# Bypass_FPGA_3V3.net
KiCad netlist of a schematic drawn in Altium Designer
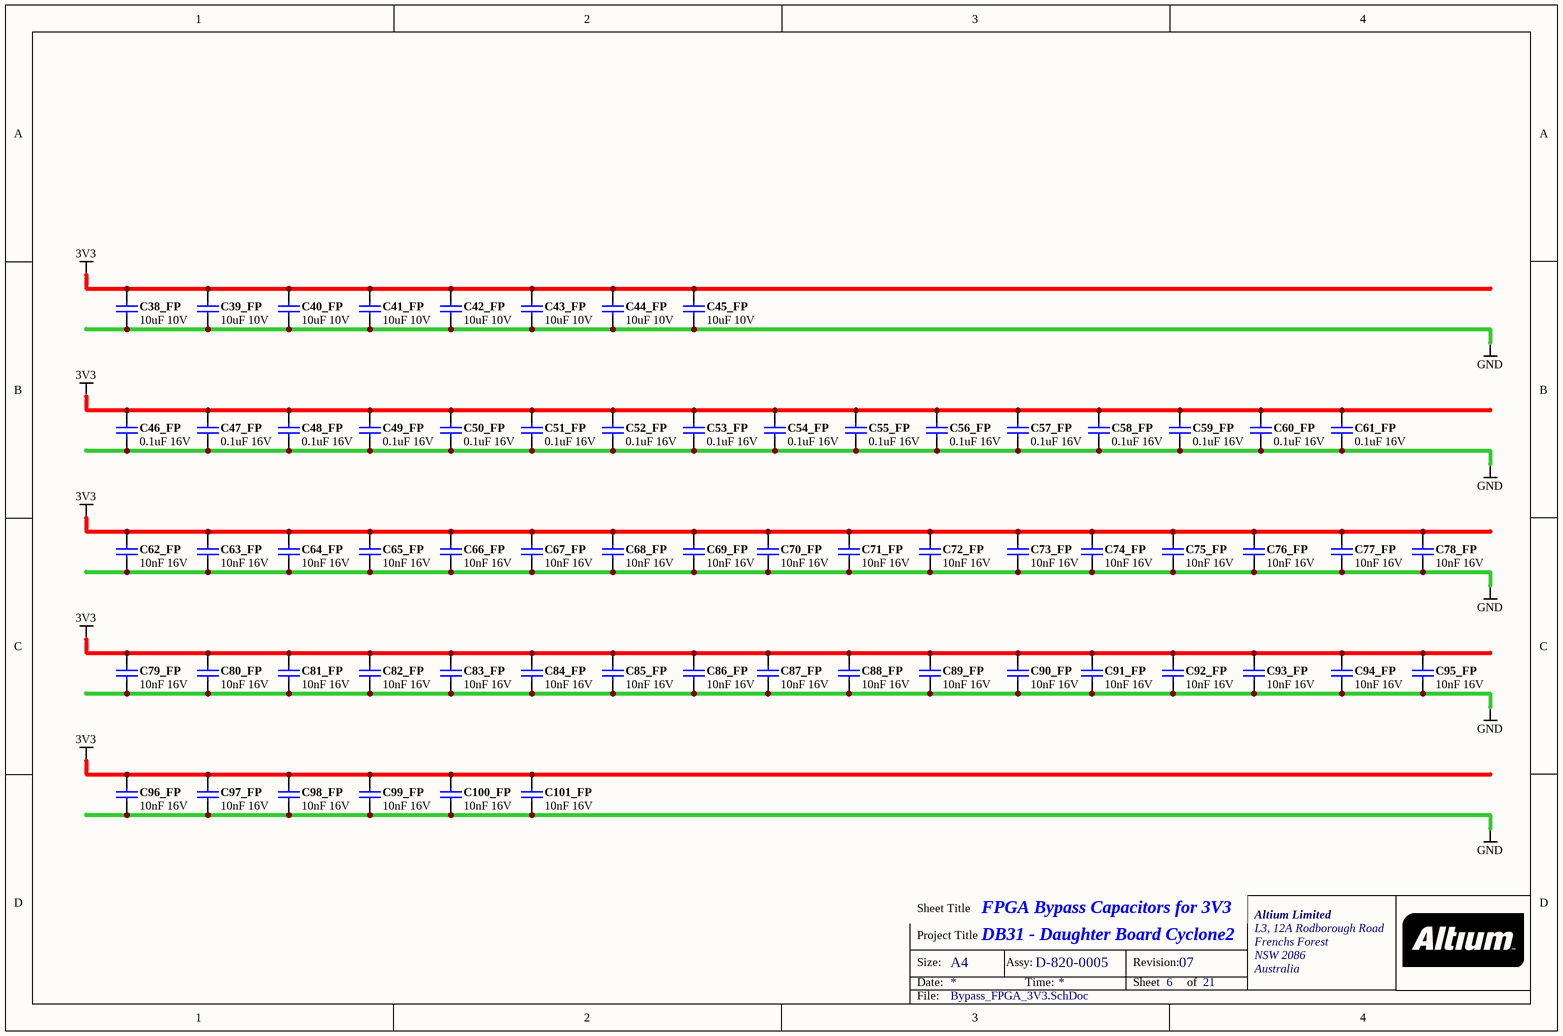
[diagram p0: Bypass_FPGA_3V3.SchDoc]

(export (version "E")
  (design (tool "Eeschema 10.0.6"))
  (components
    (comp (ref "C38_FP")
      (value "10uF 10V")
      (footprint "CAPC2012-STAR")
      (description "Capacitor, Ceramic, 10uF 10% 10V 0805 (2012) X5R")
      (fields (field (name "TOLERANCE") "10 %"))
      (libsource (lib "AltiumDesignLibrary") (part "CAP-NP"))
    )
    (comp (ref "C39_FP")
      (value "10uF 10V")
      (footprint "CAPC2012-STAR")
      (description "Capacitor, Ceramic, 10uF 10% 10V 0805 (2012) X5R")
      (fields (field (name "TOLERANCE") "10 %"))
      (libsource (lib "AltiumDesignLibrary") (part "CAP-NP"))
    )
    (comp (ref "C40_FP")
      (value "10uF 10V")
      (footprint "CAPC2012-STAR")
      (description "Capacitor, Ceramic, 10uF 10% 10V 0805 (2012) X5R")
      (fields (field (name "TOLERANCE") "10 %"))
      (libsource (lib "AltiumDesignLibrary") (part "CAP-NP"))
    )
    (comp (ref "C41_FP")
      (value "10uF 10V")
      (footprint "CAPC2012-STAR")
      (description "Capacitor, Ceramic, 10uF 10% 10V 0805 (2012) X5R")
      (fields (field (name "TOLERANCE") "10 %"))
      (libsource (lib "AltiumDesignLibrary") (part "CAP-NP"))
    )
    (comp (ref "C42_FP")
      (value "10uF 10V")
      (footprint "CAPC2012-STAR")
      (description "Capacitor, Ceramic, 10uF 10% 10V 0805 (2012) X5R")
      (fields (field (name "TOLERANCE") "10 %"))
      (libsource (lib "AltiumDesignLibrary") (part "CAP-NP"))
    )
    (comp (ref "C43_FP")
      (value "10uF 10V")
      (footprint "CAPC2012-STAR")
      (description "Capacitor, Ceramic, 10uF 10% 10V 0805 (2012) X5R")
      (fields (field (name "TOLERANCE") "10 %"))
      (libsource (lib "AltiumDesignLibrary") (part "CAP-NP"))
    )
    (comp (ref "C44_FP")
      (value "10uF 10V")
      (footprint "CAPC2012-STAR")
      (description "Capacitor, Ceramic, 10uF 10% 10V 0805 (2012) X5R")
      (fields (field (name "TOLERANCE") "10 %"))
      (libsource (lib "AltiumDesignLibrary") (part "CAP-NP"))
    )
    (comp (ref "C45_FP")
      (value "10uF 10V")
      (footprint "CAPC2012-STAR")
      (description "Capacitor, Ceramic, 10uF 10% 10V 0805 (2012) X5R")
      (fields (field (name "TOLERANCE") "10 %"))
      (libsource (lib "AltiumDesignLibrary") (part "CAP-NP"))
    )
    (comp (ref "C46_FP")
      (value "0.1uF 16V")
      (footprint "CAPC1005-STAR")
      (description "Capacitor, Ceramic, 0.1uF 10% 16V 0402 (1005) X7R")
      (fields (field (name "TOLERANCE") "10 %"))
      (libsource (lib "AltiumDesignLibrary") (part "CAP-NP"))
    )
    (comp (ref "C47_FP")
      (value "0.1uF 16V")
      (footprint "CAPC1005-STAR")
      (description "Capacitor, Ceramic, 0.1uF 10% 16V 0402 (1005) X7R")
      (fields (field (name "TOLERANCE") "10 %"))
      (libsource (lib "AltiumDesignLibrary") (part "CAP-NP"))
    )
    (comp (ref "C48_FP")
      (value "0.1uF 16V")
      (footprint "CAPC1005-STAR")
      (description "Capacitor, Ceramic, 0.1uF 10% 16V 0402 (1005) X7R")
      (fields (field (name "TOLERANCE") "10 %"))
      (libsource (lib "AltiumDesignLibrary") (part "CAP-NP"))
    )
    (comp (ref "C49_FP")
      (value "0.1uF 16V")
      (footprint "CAPC1005-STAR")
      (description "Capacitor, Ceramic, 0.1uF 10% 16V 0402 (1005) X7R")
      (fields (field (name "TOLERANCE") "10 %"))
      (libsource (lib "AltiumDesignLibrary") (part "CAP-NP"))
    )
    (comp (ref "C50_FP")
      (value "0.1uF 16V")
      (footprint "CAPC1005-STAR")
      (description "Capacitor, Ceramic, 0.1uF 10% 16V 0402 (1005) X7R")
      (fields (field (name "TOLERANCE") "10 %"))
      (libsource (lib "AltiumDesignLibrary") (part "CAP-NP"))
    )
    (comp (ref "C51_FP")
      (value "0.1uF 16V")
      (footprint "CAPC1005-STAR")
      (description "Capacitor, Ceramic, 0.1uF 10% 16V 0402 (1005) X7R")
      (fields (field (name "TOLERANCE") "10 %"))
      (libsource (lib "AltiumDesignLibrary") (part "CAP-NP"))
    )
    (comp (ref "C52_FP")
      (value "0.1uF 16V")
      (footprint "CAPC1005-STAR")
      (description "Capacitor, Ceramic, 0.1uF 10% 16V 0402 (1005) X7R")
      (fields (field (name "TOLERANCE") "10 %"))
      (libsource (lib "AltiumDesignLibrary") (part "CAP-NP"))
    )
    (comp (ref "C53_FP")
      (value "0.1uF 16V")
      (footprint "CAPC1005-STAR")
      (description "Capacitor, Ceramic, 0.1uF 10% 16V 0402 (1005) X7R")
      (fields (field (name "TOLERANCE") "10 %"))
      (libsource (lib "AltiumDesignLibrary") (part "CAP-NP"))
    )
    (comp (ref "C54_FP")
      (value "0.1uF 16V")
      (footprint "CAPC1005-STAR")
      (description "Capacitor, Ceramic, 0.1uF 10% 16V 0402 (1005) X7R")
      (fields (field (name "TOLERANCE") "10 %"))
      (libsource (lib "AltiumDesignLibrary") (part "CAP-NP"))
    )
    (comp (ref "C55_FP")
      (value "0.1uF 16V")
      (footprint "CAPC1005-STAR")
      (description "Capacitor, Ceramic, 0.1uF 10% 16V 0402 (1005) X7R")
      (fields (field (name "TOLERANCE") "10 %"))
      (libsource (lib "AltiumDesignLibrary") (part "CAP-NP"))
    )
    (comp (ref "C56_FP")
      (value "0.1uF 16V")
      (footprint "CAPC1005-STAR")
      (description "Capacitor, Ceramic, 0.1uF 10% 16V 0402 (1005) X7R")
      (fields (field (name "TOLERANCE") "10 %"))
      (libsource (lib "AltiumDesignLibrary") (part "CAP-NP"))
    )
    (comp (ref "C57_FP")
      (value "0.1uF 16V")
      (footprint "CAPC1005-STAR")
      (description "Capacitor, Ceramic, 0.1uF 10% 16V 0402 (1005) X7R")
      (fields (field (name "TOLERANCE") "10 %"))
      (libsource (lib "AltiumDesignLibrary") (part "CAP-NP"))
    )
    (comp (ref "C58_FP")
      (value "0.1uF 16V")
      (footprint "CAPC1005-STAR")
      (description "Capacitor, Ceramic, 0.1uF 10% 16V 0402 (1005) X7R")
      (fields (field (name "TOLERANCE") "10 %"))
      (libsource (lib "AltiumDesignLibrary") (part "CAP-NP"))
    )
    (comp (ref "C59_FP")
      (value "0.1uF 16V")
      (footprint "CAPC1005-STAR")
      (description "Capacitor, Ceramic, 0.1uF 10% 16V 0402 (1005) X7R")
      (fields (field (name "TOLERANCE") "10 %"))
      (libsource (lib "AltiumDesignLibrary") (part "CAP-NP"))
    )
    (comp (ref "C60_FP")
      (value "0.1uF 16V")
      (footprint "CAPC1005-STAR")
      (description "Capacitor, Ceramic, 0.1uF 10% 16V 0402 (1005) X7R")
      (fields (field (name "TOLERANCE") "10 %"))
      (libsource (lib "AltiumDesignLibrary") (part "CAP-NP"))
    )
    (comp (ref "C61_FP")
      (value "0.1uF 16V")
      (footprint "CAPC1005-STAR")
      (description "Capacitor, Ceramic, 0.1uF 10% 16V 0402 (1005) X7R")
      (fields (field (name "TOLERANCE") "10 %"))
      (libsource (lib "AltiumDesignLibrary") (part "CAP-NP"))
    )
    (comp (ref "C62_FP")
      (value "10nF 16V")
      (footprint "CAPC1005-STAR")
      (description "Capacitor, Ceramic, 10nF 10% 16V 0402 (1005) X7R")
      (fields (field (name "TOLERANCE") "10 %"))
      (libsource (lib "AltiumDesignLibrary") (part "CAP-NP"))
    )
    (comp (ref "C63_FP")
      (value "10nF 16V")
      (footprint "CAPC1005-STAR")
      (description "Capacitor, Ceramic, 10nF 10% 16V 0402 (1005) X7R")
      (fields (field (name "TOLERANCE") "10 %"))
      (libsource (lib "AltiumDesignLibrary") (part "CAP-NP"))
    )
    (comp (ref "C64_FP")
      (value "10nF 16V")
      (footprint "CAPC1005-STAR")
      (description "Capacitor, Ceramic, 10nF 10% 16V 0402 (1005) X7R")
      (fields (field (name "TOLERANCE") "10 %"))
      (libsource (lib "AltiumDesignLibrary") (part "CAP-NP"))
    )
    (comp (ref "C65_FP")
      (value "10nF 16V")
      (footprint "CAPC1005-STAR")
      (description "Capacitor, Ceramic, 10nF 10% 16V 0402 (1005) X7R")
      (fields (field (name "TOLERANCE") "10 %"))
      (libsource (lib "AltiumDesignLibrary") (part "CAP-NP"))
    )
    (comp (ref "C66_FP")
      (value "10nF 16V")
      (footprint "CAPC1005-STAR")
      (description "Capacitor, Ceramic, 10nF 10% 16V 0402 (1005) X7R")
      (fields (field (name "TOLERANCE") "10 %"))
      (libsource (lib "AltiumDesignLibrary") (part "CAP-NP"))
    )
    (comp (ref "C67_FP")
      (value "10nF 16V")
      (footprint "CAPC1005-STAR")
      (description "Capacitor, Ceramic, 10nF 10% 16V 0402 (1005) X7R")
      (fields (field (name "TOLERANCE") "10 %"))
      (libsource (lib "AltiumDesignLibrary") (part "CAP-NP"))
    )
    (comp (ref "C68_FP")
      (value "10nF 16V")
      (footprint "CAPC1005-STAR")
      (description "Capacitor, Ceramic, 10nF 10% 16V 0402 (1005) X7R")
      (fields (field (name "TOLERANCE") "10 %"))
      (libsource (lib "AltiumDesignLibrary") (part "CAP-NP"))
    )
    (comp (ref "C69_FP")
      (value "10nF 16V")
      (footprint "CAPC1005-STAR")
      (description "Capacitor, Ceramic, 10nF 10% 16V 0402 (1005) X7R")
      (fields (field (name "TOLERANCE") "10 %"))
      (libsource (lib "AltiumDesignLibrary") (part "CAP-NP"))
    )
    (comp (ref "C70_FP")
      (value "10nF 16V")
      (footprint "CAPC1005-STAR")
      (description "Capacitor, Ceramic, 10nF 10% 16V 0402 (1005) X7R")
      (fields (field (name "TOLERANCE") "10 %"))
      (libsource (lib "AltiumDesignLibrary") (part "CAP-NP"))
    )
    (comp (ref "C71_FP")
      (value "10nF 16V")
      (footprint "CAPC1005-STAR")
      (description "Capacitor, Ceramic, 10nF 10% 16V 0402 (1005) X7R")
      (fields (field (name "TOLERANCE") "10 %"))
      (libsource (lib "AltiumDesignLibrary") (part "CAP-NP"))
    )
    (comp (ref "C72_FP")
      (value "10nF 16V")
      (footprint "CAPC1005-STAR")
      (description "Capacitor, Ceramic, 10nF 10% 16V 0402 (1005) X7R")
      (fields (field (name "TOLERANCE") "10 %"))
      (libsource (lib "AltiumDesignLibrary") (part "CAP-NP"))
    )
    (comp (ref "C73_FP")
      (value "10nF 16V")
      (footprint "CAPC1005-STAR")
      (description "Capacitor, Ceramic, 10nF 10% 16V 0402 (1005) X7R")
      (fields (field (name "TOLERANCE") "10 %"))
      (libsource (lib "AltiumDesignLibrary") (part "CAP-NP"))
    )
    (comp (ref "C74_FP")
      (value "10nF 16V")
      (footprint "CAPC1005-STAR")
      (description "Capacitor, Ceramic, 10nF 10% 16V 0402 (1005) X7R")
      (fields (field (name "TOLERANCE") "10 %"))
      (libsource (lib "AltiumDesignLibrary") (part "CAP-NP"))
    )
    (comp (ref "C75_FP")
      (value "10nF 16V")
      (footprint "CAPC1005-STAR")
      (description "Capacitor, Ceramic, 10nF 10% 16V 0402 (1005) X7R")
      (fields (field (name "TOLERANCE") "10 %"))
      (libsource (lib "AltiumDesignLibrary") (part "CAP-NP"))
    )
    (comp (ref "C76_FP")
      (value "10nF 16V")
      (footprint "CAPC1005-STAR")
      (description "Capacitor, Ceramic, 10nF 10% 16V 0402 (1005) X7R")
      (fields (field (name "TOLERANCE") "10 %"))
      (libsource (lib "AltiumDesignLibrary") (part "CAP-NP"))
    )
    (comp (ref "C77_FP")
      (value "10nF 16V")
      (footprint "CAPC1005-STAR")
      (description "Capacitor, Ceramic, 10nF 10% 16V 0402 (1005) X7R")
      (fields (field (name "TOLERANCE") "10 %"))
      (libsource (lib "AltiumDesignLibrary") (part "CAP-NP"))
    )
    (comp (ref "C78_FP")
      (value "10nF 16V")
      (footprint "CAPC1005-STAR")
      (description "Capacitor, Ceramic, 10nF 10% 16V 0402 (1005) X7R")
      (fields (field (name "TOLERANCE") "10 %"))
      (libsource (lib "AltiumDesignLibrary") (part "CAP-NP"))
    )
    (comp (ref "C79_FP")
      (value "10nF 16V")
      (footprint "CAPC1005-STAR")
      (description "Capacitor, Ceramic, 10nF 10% 16V 0402 (1005) X7R")
      (fields (field (name "TOLERANCE") "10 %"))
      (libsource (lib "AltiumDesignLibrary") (part "CAP-NP"))
    )
    (comp (ref "C80_FP")
      (value "10nF 16V")
      (footprint "CAPC1005-STAR")
      (description "Capacitor, Ceramic, 10nF 10% 16V 0402 (1005) X7R")
      (fields (field (name "TOLERANCE") "10 %"))
      (libsource (lib "AltiumDesignLibrary") (part "CAP-NP"))
    )
    (comp (ref "C81_FP")
      (value "10nF 16V")
      (footprint "CAPC1005-STAR")
      (description "Capacitor, Ceramic, 10nF 10% 16V 0402 (1005) X7R")
      (fields (field (name "TOLERANCE") "10 %"))
      (libsource (lib "AltiumDesignLibrary") (part "CAP-NP"))
    )
    (comp (ref "C82_FP")
      (value "10nF 16V")
      (footprint "CAPC1005-STAR")
      (description "Capacitor, Ceramic, 10nF 10% 16V 0402 (1005) X7R")
      (fields (field (name "TOLERANCE") "10 %"))
      (libsource (lib "AltiumDesignLibrary") (part "CAP-NP"))
    )
    (comp (ref "C83_FP")
      (value "10nF 16V")
      (footprint "CAPC1005-STAR")
      (description "Capacitor, Ceramic, 10nF 10% 16V 0402 (1005) X7R")
      (fields (field (name "TOLERANCE") "10 %"))
      (libsource (lib "AltiumDesignLibrary") (part "CAP-NP"))
    )
    (comp (ref "C84_FP")
      (value "10nF 16V")
      (footprint "CAPC1005-STAR")
      (description "Capacitor, Ceramic, 10nF 10% 16V 0402 (1005) X7R")
      (fields (field (name "TOLERANCE") "10 %"))
      (libsource (lib "AltiumDesignLibrary") (part "CAP-NP"))
    )
    (comp (ref "C85_FP")
      (value "10nF 16V")
      (footprint "CAPC1005-STAR")
      (description "Capacitor, Ceramic, 10nF 10% 16V 0402 (1005) X7R")
      (fields (field (name "TOLERANCE") "10 %"))
      (libsource (lib "AltiumDesignLibrary") (part "CAP-NP"))
    )
    (comp (ref "C86_FP")
      (value "10nF 16V")
      (footprint "CAPC1005-STAR")
      (description "Capacitor, Ceramic, 10nF 10% 16V 0402 (1005) X7R")
      (fields (field (name "TOLERANCE") "10 %"))
      (libsource (lib "AltiumDesignLibrary") (part "CAP-NP"))
    )
    (comp (ref "C87_FP")
      (value "10nF 16V")
      (footprint "CAPC1005-STAR")
      (description "Capacitor, Ceramic, 10nF 10% 16V 0402 (1005) X7R")
      (fields (field (name "TOLERANCE") "10 %"))
      (libsource (lib "AltiumDesignLibrary") (part "CAP-NP"))
    )
    (comp (ref "C88_FP")
      (value "10nF 16V")
      (footprint "CAPC1005-STAR")
      (description "Capacitor, Ceramic, 10nF 10% 16V 0402 (1005) X7R")
      (fields (field (name "TOLERANCE") "10 %"))
      (libsource (lib "AltiumDesignLibrary") (part "CAP-NP"))
    )
    (comp (ref "C89_FP")
      (value "10nF 16V")
      (footprint "CAPC1005-STAR")
      (description "Capacitor, Ceramic, 10nF 10% 16V 0402 (1005) X7R")
      (fields (field (name "TOLERANCE") "10 %"))
      (libsource (lib "AltiumDesignLibrary") (part "CAP-NP"))
    )
    (comp (ref "C90_FP")
      (value "10nF 16V")
      (footprint "CAPC1005-STAR")
      (description "Capacitor, Ceramic, 10nF 10% 16V 0402 (1005) X7R")
      (fields (field (name "TOLERANCE") "10 %"))
      (libsource (lib "AltiumDesignLibrary") (part "CAP-NP"))
    )
    (comp (ref "C91_FP")
      (value "10nF 16V")
      (footprint "CAPC1005-STAR")
      (description "Capacitor, Ceramic, 10nF 10% 16V 0402 (1005) X7R")
      (fields (field (name "TOLERANCE") "10 %"))
      (libsource (lib "AltiumDesignLibrary") (part "CAP-NP"))
    )
    (comp (ref "C92_FP")
      (value "10nF 16V")
      (footprint "CAPC1005-STAR")
      (description "Capacitor, Ceramic, 10nF 10% 16V 0402 (1005) X7R")
      (fields (field (name "TOLERANCE") "10 %"))
      (libsource (lib "AltiumDesignLibrary") (part "CAP-NP"))
    )
    (comp (ref "C93_FP")
      (value "10nF 16V")
      (footprint "CAPC1005-STAR")
      (description "Capacitor, Ceramic, 10nF 10% 16V 0402 (1005) X7R")
      (fields (field (name "TOLERANCE") "10 %"))
      (libsource (lib "AltiumDesignLibrary") (part "CAP-NP"))
    )
    (comp (ref "C94_FP")
      (value "10nF 16V")
      (footprint "CAPC1005-STAR")
      (description "Capacitor, Ceramic, 10nF 10% 16V 0402 (1005) X7R")
      (fields (field (name "TOLERANCE") "10 %"))
      (libsource (lib "AltiumDesignLibrary") (part "CAP-NP"))
    )
    (comp (ref "C95_FP")
      (value "10nF 16V")
      (footprint "CAPC1005-STAR")
      (description "Capacitor, Ceramic, 10nF 10% 16V 0402 (1005) X7R")
      (fields (field (name "TOLERANCE") "10 %"))
      (libsource (lib "AltiumDesignLibrary") (part "CAP-NP"))
    )
    (comp (ref "C96_FP")
      (value "10nF 16V")
      (footprint "CAPC1005-STAR")
      (description "Capacitor, Ceramic, 10nF 10% 16V 0402 (1005) X7R")
      (fields (field (name "TOLERANCE") "10 %"))
      (libsource (lib "AltiumDesignLibrary") (part "CAP-NP"))
    )
    (comp (ref "C97_FP")
      (value "10nF 16V")
      (footprint "CAPC1005-STAR")
      (description "Capacitor, Ceramic, 10nF 10% 16V 0402 (1005) X7R")
      (fields (field (name "TOLERANCE") "10 %"))
      (libsource (lib "AltiumDesignLibrary") (part "CAP-NP"))
    )
    (comp (ref "C98_FP")
      (value "10nF 16V")
      (footprint "CAPC1005-STAR")
      (description "Capacitor, Ceramic, 10nF 10% 16V 0402 (1005) X7R")
      (fields (field (name "TOLERANCE") "10 %"))
      (libsource (lib "AltiumDesignLibrary") (part "CAP-NP"))
    )
    (comp (ref "C99_FP")
      (value "10nF 16V")
      (footprint "CAPC1005-STAR")
      (description "Capacitor, Ceramic, 10nF 10% 16V 0402 (1005) X7R")
      (fields (field (name "TOLERANCE") "10 %"))
      (libsource (lib "AltiumDesignLibrary") (part "CAP-NP"))
    )
    (comp (ref "C100_FP")
      (value "10nF 16V")
      (footprint "CAPC1005-STAR")
      (description "Capacitor, Ceramic, 10nF 10% 16V 0402 (1005) X7R")
      (fields (field (name "TOLERANCE") "10 %"))
      (libsource (lib "AltiumDesignLibrary") (part "CAP-NP"))
    )
    (comp (ref "C101_FP")
      (value "10nF 16V")
      (footprint "CAPC1005-STAR")
      (description "Capacitor, Ceramic, 10nF 10% 16V 0402 (1005) X7R")
      (fields (field (name "TOLERANCE") "10 %"))
      (libsource (lib "AltiumDesignLibrary") (part "CAP-NP"))
    )
  )
  (nets
    (net (code "1") (name "3V3") (class "Default")
      (node (ref "C100_FP") (pin "1") (pinfunction "1_1") (pintype "passive"))
      (node (ref "C101_FP") (pin "1") (pinfunction "1_1") (pintype "passive"))
      (node (ref "C38_FP") (pin "1") (pinfunction "1_1") (pintype "passive"))
      (node (ref "C39_FP") (pin "1") (pinfunction "1_1") (pintype "passive"))
      (node (ref "C40_FP") (pin "1") (pinfunction "1_1") (pintype "passive"))
      (node (ref "C41_FP") (pin "1") (pinfunction "1_1") (pintype "passive"))
      (node (ref "C42_FP") (pin "1") (pinfunction "1_1") (pintype "passive"))
      (node (ref "C43_FP") (pin "1") (pinfunction "1_1") (pintype "passive"))
      (node (ref "C44_FP") (pin "1") (pinfunction "1_1") (pintype "passive"))
      (node (ref "C45_FP") (pin "1") (pinfunction "1_1") (pintype "passive"))
      (node (ref "C46_FP") (pin "1") (pinfunction "1_1") (pintype "passive"))
      (node (ref "C47_FP") (pin "1") (pinfunction "1_1") (pintype "passive"))
      (node (ref "C48_FP") (pin "1") (pinfunction "1_1") (pintype "passive"))
      (node (ref "C49_FP") (pin "1") (pinfunction "1_1") (pintype "passive"))
      (node (ref "C50_FP") (pin "1") (pinfunction "1_1") (pintype "passive"))
      (node (ref "C51_FP") (pin "1") (pinfunction "1_1") (pintype "passive"))
      (node (ref "C52_FP") (pin "1") (pinfunction "1_1") (pintype "passive"))
      (node (ref "C53_FP") (pin "1") (pinfunction "1_1") (pintype "passive"))
      (node (ref "C54_FP") (pin "1") (pinfunction "1_1") (pintype "passive"))
      (node (ref "C55_FP") (pin "1") (pinfunction "1_1") (pintype "passive"))
      (node (ref "C56_FP") (pin "1") (pinfunction "1_1") (pintype "passive"))
      (node (ref "C57_FP") (pin "1") (pinfunction "1_1") (pintype "passive"))
      (node (ref "C58_FP") (pin "1") (pinfunction "1_1") (pintype "passive"))
      (node (ref "C59_FP") (pin "1") (pinfunction "1_1") (pintype "passive"))
      (node (ref "C60_FP") (pin "1") (pinfunction "1_1") (pintype "passive"))
      (node (ref "C61_FP") (pin "1") (pinfunction "1_1") (pintype "passive"))
      (node (ref "C62_FP") (pin "1") (pinfunction "1_1") (pintype "passive"))
      (node (ref "C63_FP") (pin "1") (pinfunction "1_1") (pintype "passive"))
      (node (ref "C64_FP") (pin "1") (pinfunction "1_1") (pintype "passive"))
      (node (ref "C65_FP") (pin "1") (pinfunction "1_1") (pintype "passive"))
      (node (ref "C66_FP") (pin "1") (pinfunction "1_1") (pintype "passive"))
      (node (ref "C67_FP") (pin "1") (pinfunction "1_1") (pintype "passive"))
      (node (ref "C68_FP") (pin "1") (pinfunction "1_1") (pintype "passive"))
      (node (ref "C69_FP") (pin "1") (pinfunction "1_1") (pintype "passive"))
      (node (ref "C70_FP") (pin "1") (pinfunction "1_1") (pintype "passive"))
      (node (ref "C71_FP") (pin "1") (pinfunction "1_1") (pintype "passive"))
      (node (ref "C72_FP") (pin "1") (pinfunction "1_1") (pintype "passive"))
      (node (ref "C73_FP") (pin "1") (pinfunction "1_1") (pintype "passive"))
      (node (ref "C74_FP") (pin "1") (pinfunction "1_1") (pintype "passive"))
      (node (ref "C75_FP") (pin "1") (pinfunction "1_1") (pintype "passive"))
      (node (ref "C76_FP") (pin "1") (pinfunction "1_1") (pintype "passive"))
      (node (ref "C77_FP") (pin "1") (pinfunction "1_1") (pintype "passive"))
      (node (ref "C78_FP") (pin "1") (pinfunction "1_1") (pintype "passive"))
      (node (ref "C79_FP") (pin "1") (pinfunction "1_1") (pintype "passive"))
      (node (ref "C80_FP") (pin "1") (pinfunction "1_1") (pintype "passive"))
      (node (ref "C81_FP") (pin "1") (pinfunction "1_1") (pintype "passive"))
      (node (ref "C82_FP") (pin "1") (pinfunction "1_1") (pintype "passive"))
      (node (ref "C83_FP") (pin "1") (pinfunction "1_1") (pintype "passive"))
      (node (ref "C84_FP") (pin "1") (pinfunction "1_1") (pintype "passive"))
      (node (ref "C85_FP") (pin "1") (pinfunction "1_1") (pintype "passive"))
      (node (ref "C86_FP") (pin "1") (pinfunction "1_1") (pintype "passive"))
      (node (ref "C87_FP") (pin "1") (pinfunction "1_1") (pintype "passive"))
      (node (ref "C88_FP") (pin "1") (pinfunction "1_1") (pintype "passive"))
      (node (ref "C89_FP") (pin "1") (pinfunction "1_1") (pintype "passive"))
      (node (ref "C90_FP") (pin "1") (pinfunction "1_1") (pintype "passive"))
      (node (ref "C91_FP") (pin "1") (pinfunction "1_1") (pintype "passive"))
      (node (ref "C92_FP") (pin "1") (pinfunction "1_1") (pintype "passive"))
      (node (ref "C93_FP") (pin "1") (pinfunction "1_1") (pintype "passive"))
      (node (ref "C94_FP") (pin "1") (pinfunction "1_1") (pintype "passive"))
      (node (ref "C95_FP") (pin "1") (pinfunction "1_1") (pintype "passive"))
      (node (ref "C96_FP") (pin "1") (pinfunction "1_1") (pintype "passive"))
      (node (ref "C97_FP") (pin "1") (pinfunction "1_1") (pintype "passive"))
      (node (ref "C98_FP") (pin "1") (pinfunction "1_1") (pintype "passive"))
      (node (ref "C99_FP") (pin "1") (pinfunction "1_1") (pintype "passive"))
    )
    (net (code "2") (name "GND") (class "Default")
      (node (ref "C100_FP") (pin "2") (pinfunction "2_2") (pintype "passive"))
      (node (ref "C101_FP") (pin "2") (pinfunction "2_2") (pintype "passive"))
      (node (ref "C38_FP") (pin "2") (pinfunction "2_2") (pintype "passive"))
      (node (ref "C39_FP") (pin "2") (pinfunction "2_2") (pintype "passive"))
      (node (ref "C40_FP") (pin "2") (pinfunction "2_2") (pintype "passive"))
      (node (ref "C41_FP") (pin "2") (pinfunction "2_2") (pintype "passive"))
      (node (ref "C42_FP") (pin "2") (pinfunction "2_2") (pintype "passive"))
      (node (ref "C43_FP") (pin "2") (pinfunction "2_2") (pintype "passive"))
      (node (ref "C44_FP") (pin "2") (pinfunction "2_2") (pintype "passive"))
      (node (ref "C45_FP") (pin "2") (pinfunction "2_2") (pintype "passive"))
      (node (ref "C46_FP") (pin "2") (pinfunction "2_2") (pintype "passive"))
      (node (ref "C47_FP") (pin "2") (pinfunction "2_2") (pintype "passive"))
      (node (ref "C48_FP") (pin "2") (pinfunction "2_2") (pintype "passive"))
      (node (ref "C49_FP") (pin "2") (pinfunction "2_2") (pintype "passive"))
      (node (ref "C50_FP") (pin "2") (pinfunction "2_2") (pintype "passive"))
      (node (ref "C51_FP") (pin "2") (pinfunction "2_2") (pintype "passive"))
      (node (ref "C52_FP") (pin "2") (pinfunction "2_2") (pintype "passive"))
      (node (ref "C53_FP") (pin "2") (pinfunction "2_2") (pintype "passive"))
      (node (ref "C54_FP") (pin "2") (pinfunction "2_2") (pintype "passive"))
      (node (ref "C55_FP") (pin "2") (pinfunction "2_2") (pintype "passive"))
      (node (ref "C56_FP") (pin "2") (pinfunction "2_2") (pintype "passive"))
      (node (ref "C57_FP") (pin "2") (pinfunction "2_2") (pintype "passive"))
      (node (ref "C58_FP") (pin "2") (pinfunction "2_2") (pintype "passive"))
      (node (ref "C59_FP") (pin "2") (pinfunction "2_2") (pintype "passive"))
      (node (ref "C60_FP") (pin "2") (pinfunction "2_2") (pintype "passive"))
      (node (ref "C61_FP") (pin "2") (pinfunction "2_2") (pintype "passive"))
      (node (ref "C62_FP") (pin "2") (pinfunction "2_2") (pintype "passive"))
      (node (ref "C63_FP") (pin "2") (pinfunction "2_2") (pintype "passive"))
      (node (ref "C64_FP") (pin "2") (pinfunction "2_2") (pintype "passive"))
      (node (ref "C65_FP") (pin "2") (pinfunction "2_2") (pintype "passive"))
      (node (ref "C66_FP") (pin "2") (pinfunction "2_2") (pintype "passive"))
      (node (ref "C67_FP") (pin "2") (pinfunction "2_2") (pintype "passive"))
      (node (ref "C68_FP") (pin "2") (pinfunction "2_2") (pintype "passive"))
      (node (ref "C69_FP") (pin "2") (pinfunction "2_2") (pintype "passive"))
      (node (ref "C70_FP") (pin "2") (pinfunction "2_2") (pintype "passive"))
      (node (ref "C71_FP") (pin "2") (pinfunction "2_2") (pintype "passive"))
      (node (ref "C72_FP") (pin "2") (pinfunction "2_2") (pintype "passive"))
      (node (ref "C73_FP") (pin "2") (pinfunction "2_2") (pintype "passive"))
      (node (ref "C74_FP") (pin "2") (pinfunction "2_2") (pintype "passive"))
      (node (ref "C75_FP") (pin "2") (pinfunction "2_2") (pintype "passive"))
      (node (ref "C76_FP") (pin "2") (pinfunction "2_2") (pintype "passive"))
      (node (ref "C77_FP") (pin "2") (pinfunction "2_2") (pintype "passive"))
      (node (ref "C78_FP") (pin "2") (pinfunction "2_2") (pintype "passive"))
      (node (ref "C79_FP") (pin "2") (pinfunction "2_2") (pintype "passive"))
      (node (ref "C80_FP") (pin "2") (pinfunction "2_2") (pintype "passive"))
      (node (ref "C81_FP") (pin "2") (pinfunction "2_2") (pintype "passive"))
      (node (ref "C82_FP") (pin "2") (pinfunction "2_2") (pintype "passive"))
      (node (ref "C83_FP") (pin "2") (pinfunction "2_2") (pintype "passive"))
      (node (ref "C84_FP") (pin "2") (pinfunction "2_2") (pintype "passive"))
      (node (ref "C85_FP") (pin "2") (pinfunction "2_2") (pintype "passive"))
      (node (ref "C86_FP") (pin "2") (pinfunction "2_2") (pintype "passive"))
      (node (ref "C87_FP") (pin "2") (pinfunction "2_2") (pintype "passive"))
      (node (ref "C88_FP") (pin "2") (pinfunction "2_2") (pintype "passive"))
      (node (ref "C89_FP") (pin "2") (pinfunction "2_2") (pintype "passive"))
      (node (ref "C90_FP") (pin "2") (pinfunction "2_2") (pintype "passive"))
      (node (ref "C91_FP") (pin "2") (pinfunction "2_2") (pintype "passive"))
      (node (ref "C92_FP") (pin "2") (pinfunction "2_2") (pintype "passive"))
      (node (ref "C93_FP") (pin "2") (pinfunction "2_2") (pintype "passive"))
      (node (ref "C94_FP") (pin "2") (pinfunction "2_2") (pintype "passive"))
      (node (ref "C95_FP") (pin "2") (pinfunction "2_2") (pintype "passive"))
      (node (ref "C96_FP") (pin "2") (pinfunction "2_2") (pintype "passive"))
      (node (ref "C97_FP") (pin "2") (pinfunction "2_2") (pintype "passive"))
      (node (ref "C98_FP") (pin "2") (pinfunction "2_2") (pintype "passive"))
      (node (ref "C99_FP") (pin "2") (pinfunction "2_2") (pintype "passive"))
    )
  )
)
